# BMS.net
KiCad netlist of a schematic drawn in Altium Designer
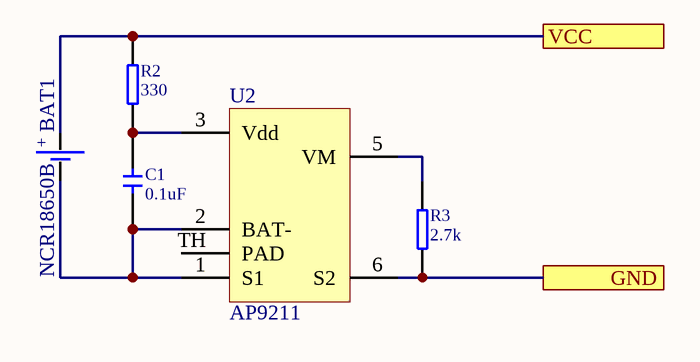
[diagram p0: BMS.SchDoc]

(export (version "E")
  (design (tool "Eeschema 10.0.6"))
  (components
    (comp (ref "BAT1")
      (value "NCR18650B")
      (footprint "BAT_18650_CLIPS")
      (description "generic battery")
      (libsource (lib "power") (part "!Battery"))
    )
    (comp (ref "C1")
      (value "0.1uF")
      (footprint "CERCAP 0402")
      (description "Capacitor")
      (fields (field (name "VOLTAGE") "50V") (field (name "Comment") "CERCAP 0402 0.1uF 50V X7R"))
      (libsource (lib "!main") (part "!Capacitor"))
    )
    (comp (ref "R2")
      (value "330")
      (footprint "RES 0402")
      (description "Resistor")
      (fields (field (name "Comment") "RES 0402 330"))
      (libsource (lib "!main") (part "!Resistor"))
    )
    (comp (ref "R3")
      (value "2.7k")
      (footprint "RES 0402")
      (description "Resistor")
      (fields (field (name "Comment") "RES 0402 2.7k"))
      (libsource (lib "!main") (part "!Resistor"))
    )
    (comp (ref "U2")
      (value "AP9211")
      (footprint "DFN-8-2x3")
      (description "BMS with built-in keys")
      (libsource (lib "power") (part "AP9211"))
    )
  )
  (nets
    (net (code "1") (name "/GND") (class "Default")
      (node (ref "R3") (pin "1") (pinfunction "11_1") (pintype "passive"))
      (node (ref "U2") (pin "6") (pinfunction "S2_6") (pintype "passive"))
    )
    (net (code "2") (name "/VCC") (class "Default")
      (node (ref "BAT1") (pin "A") (pintype "passive"))
      (node (ref "R2") (pin "2") (pinfunction "12_2") (pintype "passive"))
    )
    (net (code "3") (name "Net-(R2-11)") (class "Default")
      (node (ref "C1") (pin "2") (pintype "passive"))
      (node (ref "R2") (pin "1") (pinfunction "11_1") (pintype "passive"))
      (node (ref "U2") (pin "3") (pinfunction "Vdd_3") (pintype "passive"))
    )
    (net (code "4") (name "Net-(R3-12)") (class "Default")
      (node (ref "R3") (pin "2") (pinfunction "12_2") (pintype "passive"))
      (node (ref "U2") (pin "5") (pinfunction "VM_5") (pintype "passive"))
    )
    (net (code "5") (name "Net-(U2-BAT-)") (class "Default")
      (node (ref "BAT1") (pin "K") (pintype "passive"))
      (node (ref "C1") (pin "1") (pintype "passive"))
      (node (ref "U2") (pin "1") (pinfunction "S1_1") (pintype "passive"))
      (node (ref "U2") (pin "2") (pinfunction "BAT-_2") (pintype "passive"))
    )
    (net (code "6") (name "unconnected-(U2-PAD-PadTH)") (class "Default")
      (node (ref "U2") (pin "TH") (pinfunction "PAD_TH") (pintype "passive"))
    )
  )
)
